# snc98_3x4_Switch-cherry_ml.net
KiCad netlist of a schematic drawn in EAGLE
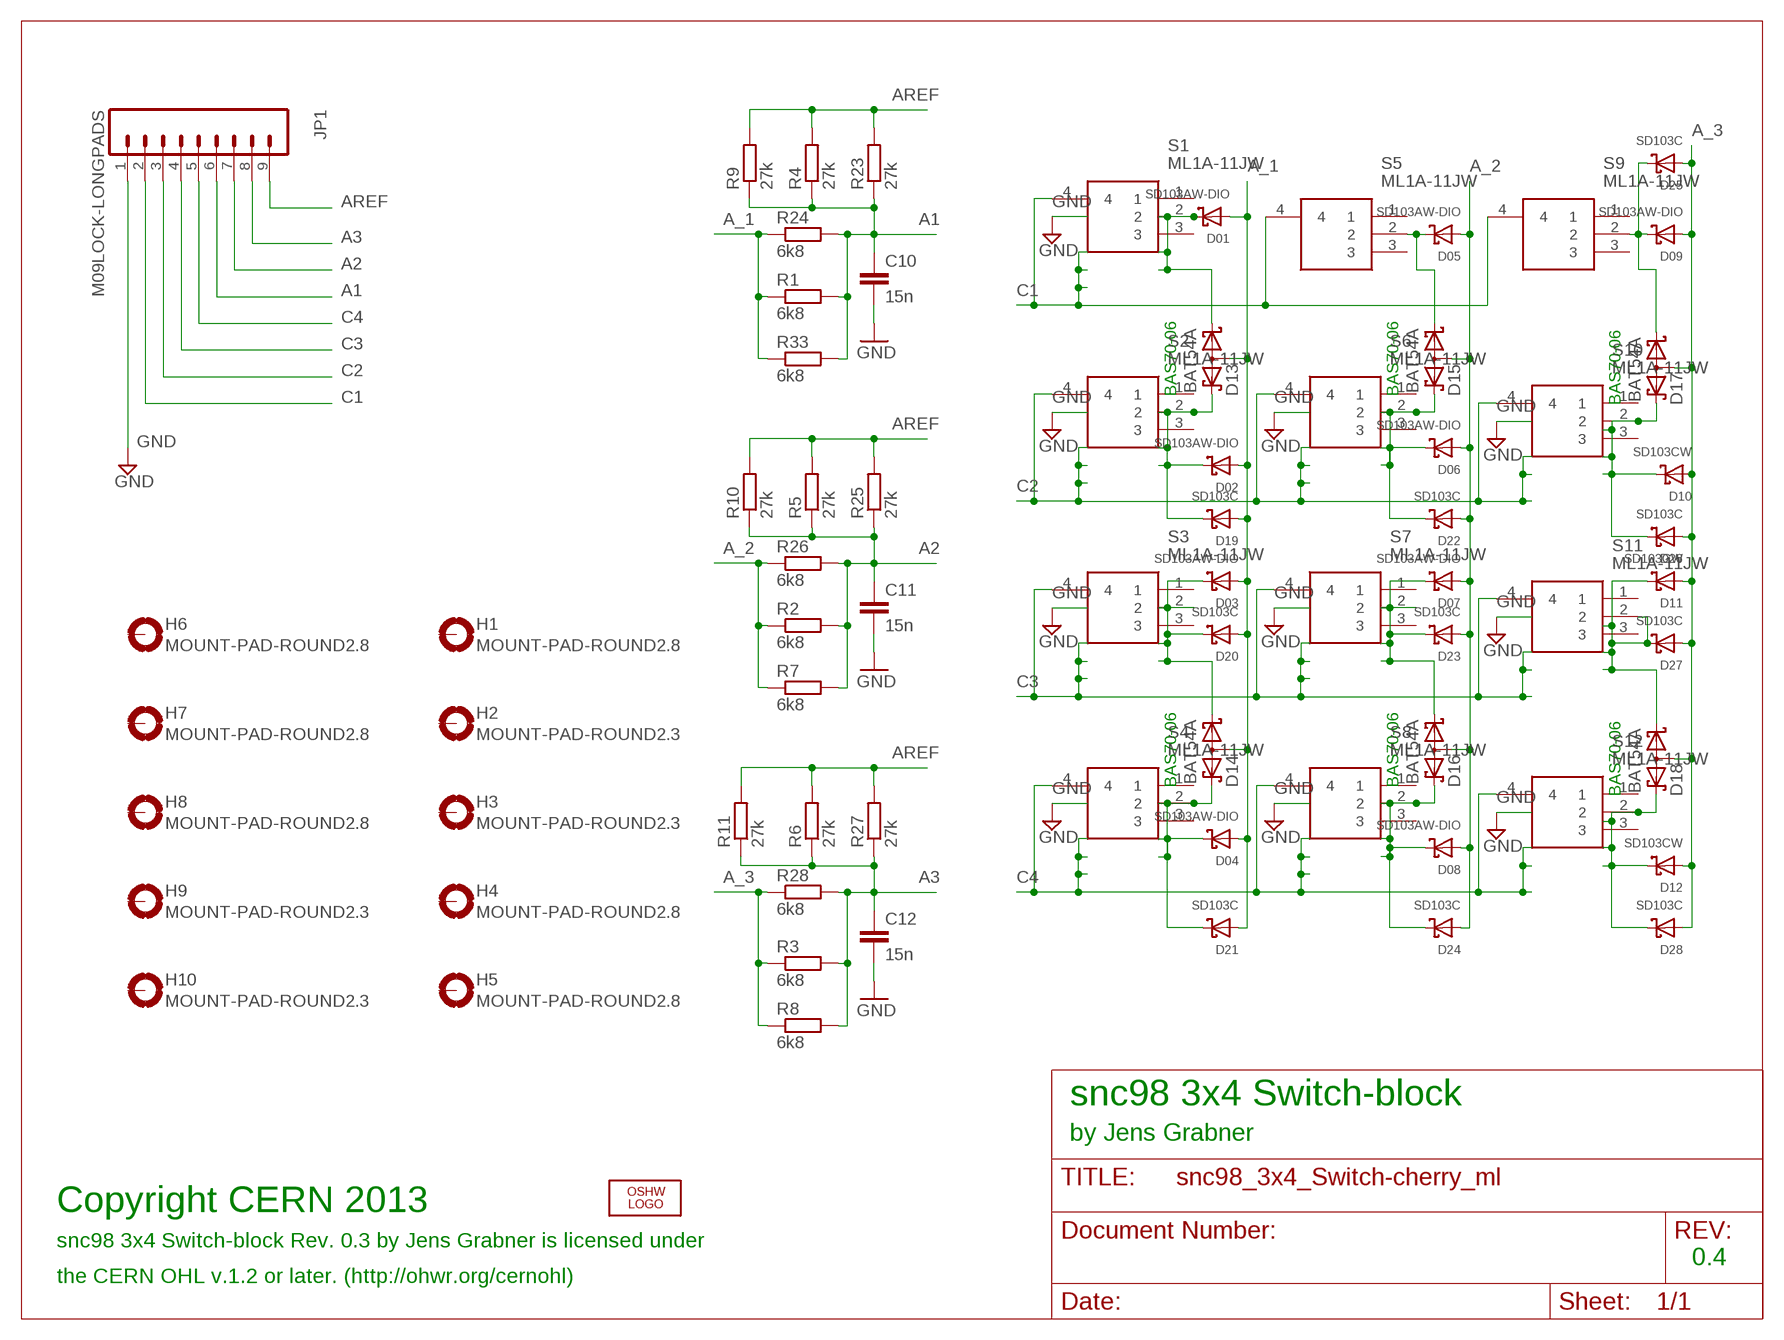
[diagram p0: schematic, sheet 1]

(export (version "E")
  (design (tool "Eeschema 10.0.6"))
  (components
    (comp (ref "C10")
      (value "15n")
      (footprint "eagle-import:C1206K")
      (libsource (lib "eagle-import") (part "C-EUC1206K"))
    )
    (comp (ref "C11")
      (value "15n")
      (footprint "eagle-import:C1206K")
      (libsource (lib "eagle-import") (part "C-EUC1206K"))
    )
    (comp (ref "C12")
      (value "15n")
      (footprint "eagle-import:C1206K")
      (libsource (lib "eagle-import") (part "C-EUC1206K"))
    )
    (comp (ref "D01")
      (value "SD103AW-DIO")
      (footprint "eagle-import:SOD-123F")
      (fields (field (name "MF") "MULTICOMP") (field (name "MPN") "SD103CW-7-F"))
      (libsource (lib "eagle-import") (part "DIODESOD-123F"))
    )
    (comp (ref "D02")
      (value "SD103AW-DIO")
      (footprint "eagle-import:SOD-123F")
      (fields (field (name "MF") "MULTICOMP") (field (name "MPN") "SD103CW-7-F"))
      (libsource (lib "eagle-import") (part "DIODESOD-123F"))
    )
    (comp (ref "D03")
      (value "SD103AW-DIO")
      (footprint "eagle-import:SOD-123F")
      (fields (field (name "MF") "MULTICOMP") (field (name "MPN") "SD103CW-7-F"))
      (libsource (lib "eagle-import") (part "DIODESOD-123F"))
    )
    (comp (ref "D04")
      (value "SD103AW-DIO")
      (footprint "eagle-import:SOD-123F")
      (fields (field (name "MF") "MULTICOMP") (field (name "MPN") "SD103CW-7-F"))
      (libsource (lib "eagle-import") (part "DIODESOD-123F"))
    )
    (comp (ref "D05")
      (value "SD103AW-DIO")
      (footprint "eagle-import:SOD-123F")
      (fields (field (name "MF") "MULTICOMP") (field (name "MPN") "SD103CW-7-F"))
      (libsource (lib "eagle-import") (part "DIODESOD-123F"))
    )
    (comp (ref "D06")
      (value "SD103AW-DIO")
      (footprint "eagle-import:SOD-123F")
      (fields (field (name "MF") "MULTICOMP") (field (name "MPN") "SD103CW-7-F"))
      (libsource (lib "eagle-import") (part "DIODESOD-123F"))
    )
    (comp (ref "D07")
      (value "SD103AW-DIO")
      (footprint "eagle-import:SOD-123F")
      (fields (field (name "MF") "MULTICOMP") (field (name "MPN") "SD103CW-7-F"))
      (libsource (lib "eagle-import") (part "DIODESOD-123F"))
    )
    (comp (ref "D08")
      (value "SD103AW-DIO")
      (footprint "eagle-import:SOD-123F")
      (fields (field (name "MF") "MULTICOMP") (field (name "MPN") "SD103CW-7-F"))
      (libsource (lib "eagle-import") (part "DIODESOD-123F"))
    )
    (comp (ref "D09")
      (value "SD103AW-DIO")
      (footprint "eagle-import:SOD-123F")
      (fields (field (name "MF") "MULTICOMP") (field (name "MPN") "SD103CW-7-F"))
      (libsource (lib "eagle-import") (part "DIODESOD-123F"))
    )
    (comp (ref "D10")
      (value "SD103CW")
      (footprint "eagle-import:SOD-123F")
      (fields (field (name "MF") "MULTICOMP") (field (name "MPN") "SD103CW-7-F"))
      (libsource (lib "eagle-import") (part "DIODESOD-123F"))
    )
    (comp (ref "D11")
      (value "SD103CW")
      (footprint "eagle-import:SOD-123F")
      (fields (field (name "MF") "MULTICOMP") (field (name "MPN") "SD103CW-7-F"))
      (libsource (lib "eagle-import") (part "DIODESOD-123F"))
    )
    (comp (ref "D12")
      (value "SD103CW")
      (footprint "eagle-import:SOD-123F")
      (fields (field (name "MF") "MULTICOMP") (field (name "MPN") "SD103CW-7-F"))
      (libsource (lib "eagle-import") (part "DIODESOD-123F"))
    )
    (comp (ref "D13")
      (value "BAT54A")
      (footprint "eagle-import:SOT23")
      (libsource (lib "eagle-import") (part "BAT54A"))
    )
    (comp (ref "D14")
      (value "BAT54A")
      (footprint "eagle-import:SOT23")
      (libsource (lib "eagle-import") (part "BAT54A"))
    )
    (comp (ref "D15")
      (value "BAT54A")
      (footprint "eagle-import:SOT23")
      (libsource (lib "eagle-import") (part "BAT54A"))
    )
    (comp (ref "D16")
      (value "BAT54A")
      (footprint "eagle-import:SOT23")
      (libsource (lib "eagle-import") (part "BAT54A"))
    )
    (comp (ref "D17")
      (value "BAT54A")
      (footprint "eagle-import:SOT23")
      (libsource (lib "eagle-import") (part "BAT54A"))
    )
    (comp (ref "D18")
      (value "BAT54A")
      (footprint "eagle-import:SOT23")
      (libsource (lib "eagle-import") (part "BAT54A"))
    )
    (comp (ref "D19")
      (value "SD103C")
      (footprint "eagle-import:280MIL-TH")
      (fields (field (name "MF") "MULTICOMP") (field (name "MPN") "SD103CW-7-F"))
      (libsource (lib "eagle-import") (part "DIODE280MIL-TH"))
    )
    (comp (ref "D20")
      (value "SD103C")
      (footprint "eagle-import:280MIL-TH")
      (fields (field (name "MF") "MULTICOMP") (field (name "MPN") "SD103CW-7-F"))
      (libsource (lib "eagle-import") (part "DIODE280MIL-TH"))
    )
    (comp (ref "D21")
      (value "SD103C")
      (footprint "eagle-import:280MIL-TH")
      (fields (field (name "MF") "MULTICOMP") (field (name "MPN") "SD103CW-7-F"))
      (libsource (lib "eagle-import") (part "DIODE280MIL-TH"))
    )
    (comp (ref "D22")
      (value "SD103C")
      (footprint "eagle-import:280MIL-TH")
      (fields (field (name "MF") "MULTICOMP") (field (name "MPN") "SD103CW-7-F"))
      (libsource (lib "eagle-import") (part "DIODE280MIL-TH"))
    )
    (comp (ref "D23")
      (value "SD103C")
      (footprint "eagle-import:280MIL-TH")
      (fields (field (name "MF") "MULTICOMP") (field (name "MPN") "SD103CW-7-F"))
      (libsource (lib "eagle-import") (part "DIODE280MIL-TH"))
    )
    (comp (ref "D24")
      (value "SD103C")
      (footprint "eagle-import:280MIL-TH")
      (fields (field (name "MF") "MULTICOMP") (field (name "MPN") "SD103CW-7-F"))
      (libsource (lib "eagle-import") (part "DIODE280MIL-TH"))
    )
    (comp (ref "D25")
      (value "SD103C")
      (footprint "eagle-import:280MIL-TH")
      (fields (field (name "MF") "MULTICOMP") (field (name "MPN") "SD103CW-7-F"))
      (libsource (lib "eagle-import") (part "DIODE280MIL-TH"))
    )
    (comp (ref "D26")
      (value "SD103C")
      (footprint "eagle-import:280MIL-TH")
      (fields (field (name "MF") "MULTICOMP") (field (name "MPN") "SD103CW-7-F"))
      (libsource (lib "eagle-import") (part "DIODE280MIL-TH"))
    )
    (comp (ref "D27")
      (value "SD103C")
      (footprint "eagle-import:280MIL-TH")
      (fields (field (name "MF") "MULTICOMP") (field (name "MPN") "SD103CW-7-F"))
      (libsource (lib "eagle-import") (part "DIODE280MIL-TH"))
    )
    (comp (ref "D28")
      (value "SD103C")
      (footprint "eagle-import:280MIL-TH")
      (fields (field (name "MF") "MULTICOMP") (field (name "MPN") "SD103CW-7-F"))
      (libsource (lib "eagle-import") (part "DIODE280MIL-TH"))
    )
    (comp (ref "H1")
      (value "MOUNT-PAD-ROUND2.8")
      (footprint "eagle-import:2,8-PAD")
      (libsource (lib "eagle-import") (part "MOUNT-PAD-ROUND2.8"))
    )
    (comp (ref "H2")
      (value "MOUNT-PAD-ROUND2.3")
      (footprint "eagle-import:2,3-PAD")
      (libsource (lib "eagle-import") (part "MOUNT-PAD-ROUND2.3"))
    )
    (comp (ref "H3")
      (value "MOUNT-PAD-ROUND2.3")
      (footprint "eagle-import:2,3-PAD")
      (libsource (lib "eagle-import") (part "MOUNT-PAD-ROUND2.3"))
    )
    (comp (ref "H4")
      (value "MOUNT-PAD-ROUND2.8")
      (footprint "eagle-import:2,8-PAD")
      (libsource (lib "eagle-import") (part "MOUNT-PAD-ROUND2.8"))
    )
    (comp (ref "H5")
      (value "MOUNT-PAD-ROUND2.8")
      (footprint "eagle-import:2,8-PAD")
      (libsource (lib "eagle-import") (part "MOUNT-PAD-ROUND2.8"))
    )
    (comp (ref "H6")
      (value "MOUNT-PAD-ROUND2.8")
      (footprint "eagle-import:2,8-PAD")
      (libsource (lib "eagle-import") (part "MOUNT-PAD-ROUND2.8"))
    )
    (comp (ref "H7")
      (value "MOUNT-PAD-ROUND2.8")
      (footprint "eagle-import:2,8-PAD")
      (libsource (lib "eagle-import") (part "MOUNT-PAD-ROUND2.8"))
    )
    (comp (ref "H8")
      (value "MOUNT-PAD-ROUND2.8")
      (footprint "eagle-import:2,8-PAD")
      (libsource (lib "eagle-import") (part "MOUNT-PAD-ROUND2.8"))
    )
    (comp (ref "H9")
      (value "MOUNT-PAD-ROUND2.3")
      (footprint "eagle-import:2,3-PAD")
      (libsource (lib "eagle-import") (part "MOUNT-PAD-ROUND2.3"))
    )
    (comp (ref "H10")
      (value "MOUNT-PAD-ROUND2.3")
      (footprint "eagle-import:2,3-PAD")
      (libsource (lib "eagle-import") (part "MOUNT-PAD-ROUND2.3"))
    )
    (comp (ref "JP1")
      (value "M09LOCK-LONGPADS")
      (footprint "eagle-import:1X09_LOCK_LONGPADS")
      (libsource (lib "eagle-import") (part "M09LOCK-LONGPADS"))
    )
    (comp (ref "LOGO1")
      (value "OSHW_LOGO_8MILX0150-NT")
      (footprint "eagle-import:OSHW_8X150_NOTEXT")
      (libsource (lib "eagle-import") (part "OSHW_LOGO_8MILX0150-NT"))
    )
    (comp (ref "R1")
      (value "6k8")
      (footprint "eagle-import:R1206")
      (libsource (lib "eagle-import") (part "R-EU_R1206"))
    )
    (comp (ref "R2")
      (value "6k8")
      (footprint "eagle-import:R1206")
      (libsource (lib "eagle-import") (part "R-EU_R1206"))
    )
    (comp (ref "R3")
      (value "6k8")
      (footprint "eagle-import:R1206")
      (libsource (lib "eagle-import") (part "R-EU_R1206"))
    )
    (comp (ref "R4")
      (value "27k")
      (footprint "eagle-import:R1206")
      (libsource (lib "eagle-import") (part "R-EU_R1206"))
    )
    (comp (ref "R5")
      (value "27k")
      (footprint "eagle-import:R1206")
      (libsource (lib "eagle-import") (part "R-EU_R1206"))
    )
    (comp (ref "R6")
      (value "27k")
      (footprint "eagle-import:R1206")
      (libsource (lib "eagle-import") (part "R-EU_R1206"))
    )
    (comp (ref "R7")
      (value "6k8")
      (footprint "eagle-import:M0805")
      (libsource (lib "eagle-import") (part "R-EU_M0805"))
    )
    (comp (ref "R8")
      (value "6k8")
      (footprint "eagle-import:M0805")
      (libsource (lib "eagle-import") (part "R-EU_M0805"))
    )
    (comp (ref "R9")
      (value "27k")
      (footprint "eagle-import:M0805")
      (libsource (lib "eagle-import") (part "R-EU_M0805"))
    )
    (comp (ref "R10")
      (value "27k")
      (footprint "eagle-import:M0805")
      (libsource (lib "eagle-import") (part "R-EU_M0805"))
    )
    (comp (ref "R11")
      (value "27k")
      (footprint "eagle-import:M0805")
      (libsource (lib "eagle-import") (part "R-EU_M0805"))
    )
    (comp (ref "R23")
      (value "27k")
      (footprint "eagle-import:0204_5")
      (libsource (lib "eagle-import") (part "R-EU_0204/5"))
    )
    (comp (ref "R24")
      (value "6k8")
      (footprint "eagle-import:0204_5")
      (libsource (lib "eagle-import") (part "R-EU_0204/5"))
    )
    (comp (ref "R25")
      (value "27k")
      (footprint "eagle-import:0204_5")
      (libsource (lib "eagle-import") (part "R-EU_0204/5"))
    )
    (comp (ref "R26")
      (value "6k8")
      (footprint "eagle-import:0204_5")
      (libsource (lib "eagle-import") (part "R-EU_0204/5"))
    )
    (comp (ref "R27")
      (value "27k")
      (footprint "eagle-import:0204_5")
      (libsource (lib "eagle-import") (part "R-EU_0204/5"))
    )
    (comp (ref "R28")
      (value "6k8")
      (footprint "eagle-import:0204_5")
      (libsource (lib "eagle-import") (part "R-EU_0204/5"))
    )
    (comp (ref "R33")
      (value "6k8")
      (footprint "eagle-import:M0805")
      (libsource (lib "eagle-import") (part "R-EU_M0805"))
    )
    (comp (ref "S1")
      (value "ML1A-11JW")
      (footprint "eagle-import:ML1A11JW")
      (fields (field (name "MOUSER_PART_NUMBER") "540-ML1A-11JW"))
      (libsource (lib "eagle-import") (part "ML1A-11JW"))
    )
    (comp (ref "S2")
      (value "ML1A-11JW")
      (footprint "eagle-import:ML1A11JW")
      (fields (field (name "MOUSER_PART_NUMBER") "540-ML1A-11JW"))
      (libsource (lib "eagle-import") (part "ML1A-11JW"))
    )
    (comp (ref "S3")
      (value "ML1A-11JW")
      (footprint "eagle-import:ML1A11JW")
      (fields (field (name "MOUSER_PART_NUMBER") "540-ML1A-11JW"))
      (libsource (lib "eagle-import") (part "ML1A-11JW"))
    )
    (comp (ref "S4")
      (value "ML1A-11JW")
      (footprint "eagle-import:ML1A11JW")
      (fields (field (name "MOUSER_PART_NUMBER") "540-ML1A-11JW"))
      (libsource (lib "eagle-import") (part "ML1A-11JW"))
    )
    (comp (ref "S5")
      (value "ML1A-11JW")
      (footprint "eagle-import:ML1A11JW")
      (fields (field (name "MOUSER_PART_NUMBER") "540-ML1A-11JW"))
      (libsource (lib "eagle-import") (part "ML1A-11JW"))
    )
    (comp (ref "S6")
      (value "ML1A-11JW")
      (footprint "eagle-import:ML1A11JW")
      (fields (field (name "MOUSER_PART_NUMBER") "540-ML1A-11JW"))
      (libsource (lib "eagle-import") (part "ML1A-11JW"))
    )
    (comp (ref "S7")
      (value "ML1A-11JW")
      (footprint "eagle-import:ML1A11JW")
      (fields (field (name "MOUSER_PART_NUMBER") "540-ML1A-11JW"))
      (libsource (lib "eagle-import") (part "ML1A-11JW"))
    )
    (comp (ref "S8")
      (value "ML1A-11JW")
      (footprint "eagle-import:ML1A11JW")
      (fields (field (name "MOUSER_PART_NUMBER") "540-ML1A-11JW"))
      (libsource (lib "eagle-import") (part "ML1A-11JW"))
    )
    (comp (ref "S9")
      (value "ML1A-11JW")
      (footprint "eagle-import:ML1A11JW")
      (fields (field (name "MOUSER_PART_NUMBER") "540-ML1A-11JW"))
      (libsource (lib "eagle-import") (part "ML1A-11JW"))
    )
    (comp (ref "S10")
      (value "ML1A-11JW")
      (footprint "eagle-import:ML1A11JW")
      (fields (field (name "MOUSER_PART_NUMBER") "540-ML1A-11JW"))
      (libsource (lib "eagle-import") (part "ML1A-11JW"))
    )
    (comp (ref "S11")
      (value "ML1A-11JW")
      (footprint "eagle-import:ML1A11JW")
      (fields (field (name "MOUSER_PART_NUMBER") "540-ML1A-11JW"))
      (libsource (lib "eagle-import") (part "ML1A-11JW"))
    )
    (comp (ref "S12")
      (value "ML1A-11JW")
      (footprint "eagle-import:ML1A11JW")
      (fields (field (name "MOUSER_PART_NUMBER") "540-ML1A-11JW"))
      (libsource (lib "eagle-import") (part "ML1A-11JW"))
    )
  )
  (nets
    (net (code "1") (name "/A1") (class "Default")
      (node (ref "C10") (pin "1") (pinfunction "1_1") (pintype "passive"))
      (node (ref "JP1") (pin "6") (pinfunction "6_6") (pintype "passive"))
      (node (ref "R1") (pin "2") (pinfunction "2_2") (pintype "passive"))
      (node (ref "R23") (pin "1") (pinfunction "1_1") (pintype "passive"))
      (node (ref "R24") (pin "2") (pinfunction "2_2") (pintype "passive"))
      (node (ref "R33") (pin "2") (pinfunction "2_2") (pintype "passive"))
      (node (ref "R4") (pin "1") (pinfunction "1_1") (pintype "passive"))
      (node (ref "R9") (pin "1") (pinfunction "1_1") (pintype "passive"))
    )
    (net (code "2") (name "/A2") (class "Default")
      (node (ref "C11") (pin "1") (pinfunction "1_1") (pintype "passive"))
      (node (ref "JP1") (pin "7") (pinfunction "7_7") (pintype "passive"))
      (node (ref "R10") (pin "1") (pinfunction "1_1") (pintype "passive"))
      (node (ref "R2") (pin "2") (pinfunction "2_2") (pintype "passive"))
      (node (ref "R25") (pin "1") (pinfunction "1_1") (pintype "passive"))
      (node (ref "R26") (pin "2") (pinfunction "2_2") (pintype "passive"))
      (node (ref "R5") (pin "1") (pinfunction "1_1") (pintype "passive"))
      (node (ref "R7") (pin "2") (pinfunction "2_2") (pintype "passive"))
    )
    (net (code "3") (name "/A3") (class "Default")
      (node (ref "C12") (pin "1") (pinfunction "1_1") (pintype "passive"))
      (node (ref "JP1") (pin "8") (pinfunction "8_8") (pintype "passive"))
      (node (ref "R11") (pin "1") (pinfunction "1_1") (pintype "passive"))
      (node (ref "R27") (pin "1") (pinfunction "1_1") (pintype "passive"))
      (node (ref "R28") (pin "2") (pinfunction "2_2") (pintype "passive"))
      (node (ref "R3") (pin "2") (pinfunction "2_2") (pintype "passive"))
      (node (ref "R6") (pin "1") (pinfunction "1_1") (pintype "passive"))
      (node (ref "R8") (pin "2") (pinfunction "2_2") (pintype "passive"))
    )
    (net (code "4") (name "/AREF") (class "Default")
      (node (ref "JP1") (pin "9") (pinfunction "9_9") (pintype "passive"))
      (node (ref "R10") (pin "2") (pinfunction "2_2") (pintype "passive"))
      (node (ref "R11") (pin "2") (pinfunction "2_2") (pintype "passive"))
      (node (ref "R23") (pin "2") (pinfunction "2_2") (pintype "passive"))
      (node (ref "R25") (pin "2") (pinfunction "2_2") (pintype "passive"))
      (node (ref "R27") (pin "2") (pinfunction "2_2") (pintype "passive"))
      (node (ref "R4") (pin "2") (pinfunction "2_2") (pintype "passive"))
      (node (ref "R5") (pin "2") (pinfunction "2_2") (pintype "passive"))
      (node (ref "R6") (pin "2") (pinfunction "2_2") (pintype "passive"))
      (node (ref "R9") (pin "2") (pinfunction "2_2") (pintype "passive"))
    )
    (net (code "5") (name "/A_1") (class "Default")
      (node (ref "D01") (pin "A") (pinfunction "A_A") (pintype "passive"))
      (node (ref "D02") (pin "A") (pinfunction "A_A") (pintype "passive"))
      (node (ref "D03") (pin "A") (pinfunction "A_A") (pintype "passive"))
      (node (ref "D04") (pin "A") (pinfunction "A_A") (pintype "passive"))
      (node (ref "D13") (pin "3") (pinfunction "AA_3") (pintype "passive"))
      (node (ref "D14") (pin "3") (pinfunction "AA_3") (pintype "passive"))
      (node (ref "D19") (pin "P$1") (pinfunction "A_P$1") (pintype "passive"))
      (node (ref "D20") (pin "P$1") (pinfunction "A_P$1") (pintype "passive"))
      (node (ref "D21") (pin "P$1") (pinfunction "A_P$1") (pintype "passive"))
      (node (ref "R1") (pin "1") (pinfunction "1_1") (pintype "passive"))
      (node (ref "R24") (pin "1") (pinfunction "1_1") (pintype "passive"))
      (node (ref "R33") (pin "1") (pinfunction "1_1") (pintype "passive"))
    )
    (net (code "6") (name "/A_2") (class "Default")
      (node (ref "D05") (pin "A") (pinfunction "A_A") (pintype "passive"))
      (node (ref "D06") (pin "A") (pinfunction "A_A") (pintype "passive"))
      (node (ref "D07") (pin "A") (pinfunction "A_A") (pintype "passive"))
      (node (ref "D08") (pin "A") (pinfunction "A_A") (pintype "passive"))
      (node (ref "D15") (pin "3") (pinfunction "AA_3") (pintype "passive"))
      (node (ref "D16") (pin "3") (pinfunction "AA_3") (pintype "passive"))
      (node (ref "D22") (pin "P$1") (pinfunction "A_P$1") (pintype "passive"))
      (node (ref "D23") (pin "P$1") (pinfunction "A_P$1") (pintype "passive"))
      (node (ref "D24") (pin "P$1") (pinfunction "A_P$1") (pintype "passive"))
      (node (ref "R2") (pin "1") (pinfunction "1_1") (pintype "passive"))
      (node (ref "R26") (pin "1") (pinfunction "1_1") (pintype "passive"))
      (node (ref "R7") (pin "1") (pinfunction "1_1") (pintype "passive"))
    )
    (net (code "7") (name "/A_3") (class "Default")
      (node (ref "D09") (pin "A") (pinfunction "A_A") (pintype "passive"))
      (node (ref "D10") (pin "A") (pinfunction "A_A") (pintype "passive"))
      (node (ref "D11") (pin "A") (pinfunction "A_A") (pintype "passive"))
      (node (ref "D12") (pin "A") (pinfunction "A_A") (pintype "passive"))
      (node (ref "D17") (pin "3") (pinfunction "AA_3") (pintype "passive"))
      (node (ref "D18") (pin "3") (pinfunction "AA_3") (pintype "passive"))
      (node (ref "D25") (pin "P$1") (pinfunction "A_P$1") (pintype "passive"))
      (node (ref "D26") (pin "P$1") (pinfunction "A_P$1") (pintype "passive"))
      (node (ref "D27") (pin "P$1") (pinfunction "A_P$1") (pintype "passive"))
      (node (ref "D28") (pin "P$1") (pinfunction "A_P$1") (pintype "passive"))
      (node (ref "R28") (pin "1") (pinfunction "1_1") (pintype "passive"))
      (node (ref "R3") (pin "1") (pinfunction "1_1") (pintype "passive"))
      (node (ref "R8") (pin "1") (pinfunction "1_1") (pintype "passive"))
    )
    (net (code "8") (name "/C1") (class "Default")
      (node (ref "JP1") (pin "2") (pinfunction "2_2") (pintype "passive"))
      (node (ref "S1") (pin "4") (pinfunction "4_4") (pintype "bidirectional"))
      (node (ref "S5") (pin "4") (pinfunction "4_4") (pintype "bidirectional"))
      (node (ref "S9") (pin "4") (pinfunction "4_4") (pintype "bidirectional"))
    )
    (net (code "9") (name "/C2") (class "Default")
      (node (ref "JP1") (pin "3") (pinfunction "3_3") (pintype "passive"))
      (node (ref "S10") (pin "4") (pinfunction "4_4") (pintype "bidirectional"))
      (node (ref "S2") (pin "4") (pinfunction "4_4") (pintype "bidirectional"))
      (node (ref "S6") (pin "4") (pinfunction "4_4") (pintype "bidirectional"))
    )
    (net (code "10") (name "/C3") (class "Default")
      (node (ref "JP1") (pin "4") (pinfunction "4_4") (pintype "passive"))
      (node (ref "S11") (pin "4") (pinfunction "4_4") (pintype "bidirectional"))
      (node (ref "S3") (pin "4") (pinfunction "4_4") (pintype "bidirectional"))
      (node (ref "S7") (pin "4") (pinfunction "4_4") (pintype "bidirectional"))
    )
    (net (code "11") (name "/C4") (class "Default")
      (node (ref "JP1") (pin "5") (pinfunction "5_5") (pintype "passive"))
      (node (ref "S12") (pin "4") (pinfunction "4_4") (pintype "bidirectional"))
      (node (ref "S4") (pin "4") (pinfunction "4_4") (pintype "bidirectional"))
      (node (ref "S8") (pin "4") (pinfunction "4_4") (pintype "bidirectional"))
    )
    (net (code "12") (name "GND") (class "Default")
      (node (ref "C10") (pin "2") (pinfunction "2_2") (pintype "passive"))
      (node (ref "C11") (pin "2") (pinfunction "2_2") (pintype "passive"))
      (node (ref "C12") (pin "2") (pinfunction "2_2") (pintype "passive"))
      (node (ref "JP1") (pin "1") (pinfunction "1_1") (pintype "passive"))
    )
    (net (code "13") (name "Net-(D13-K1)") (class "Default")
      (node (ref "D01") (pin "C") (pinfunction "C_C") (pintype "passive"))
      (node (ref "D13") (pin "1") (pinfunction "K1_1") (pintype "passive"))
      (node (ref "S1") (pin "2") (pinfunction "2_2") (pintype "bidirectional"))
    )
    (net (code "14") (name "Net-(D13-K2)") (class "Default")
      (node (ref "D02") (pin "C") (pinfunction "C_C") (pintype "passive"))
      (node (ref "D13") (pin "2") (pinfunction "K2_2") (pintype "passive"))
      (node (ref "D19") (pin "P$2") (pinfunction "C_P$2") (pintype "passive"))
      (node (ref "S2") (pin "2") (pinfunction "2_2") (pintype "bidirectional"))
    )
    (net (code "15") (name "Net-(D14-K1)") (class "Default")
      (node (ref "D03") (pin "C") (pinfunction "C_C") (pintype "passive"))
      (node (ref "D14") (pin "1") (pinfunction "K1_1") (pintype "passive"))
      (node (ref "D20") (pin "P$2") (pinfunction "C_P$2") (pintype "passive"))
      (node (ref "S3") (pin "2") (pinfunction "2_2") (pintype "bidirectional"))
    )
    (net (code "16") (name "Net-(D14-K2)") (class "Default")
      (node (ref "D04") (pin "C") (pinfunction "C_C") (pintype "passive"))
      (node (ref "D14") (pin "2") (pinfunction "K2_2") (pintype "passive"))
      (node (ref "D21") (pin "P$2") (pinfunction "C_P$2") (pintype "passive"))
      (node (ref "S4") (pin "2") (pinfunction "2_2") (pintype "bidirectional"))
    )
    (net (code "17") (name "Net-(D15-K1)") (class "Default")
      (node (ref "D05") (pin "C") (pinfunction "C_C") (pintype "passive"))
      (node (ref "D15") (pin "1") (pinfunction "K1_1") (pintype "passive"))
      (node (ref "S5") (pin "2") (pinfunction "2_2") (pintype "bidirectional"))
    )
    (net (code "18") (name "Net-(D15-K2)") (class "Default")
      (node (ref "D06") (pin "C") (pinfunction "C_C") (pintype "passive"))
      (node (ref "D15") (pin "2") (pinfunction "K2_2") (pintype "passive"))
      (node (ref "D22") (pin "P$2") (pinfunction "C_P$2") (pintype "passive"))
      (node (ref "S6") (pin "2") (pinfunction "2_2") (pintype "bidirectional"))
    )
    (net (code "19") (name "Net-(D16-K1)") (class "Default")
      (node (ref "D07") (pin "C") (pinfunction "C_C") (pintype "passive"))
      (node (ref "D16") (pin "1") (pinfunction "K1_1") (pintype "passive"))
      (node (ref "D23") (pin "P$2") (pinfunction "C_P$2") (pintype "passive"))
      (node (ref "S7") (pin "2") (pinfunction "2_2") (pintype "bidirectional"))
    )
    (net (code "20") (name "Net-(D16-K2)") (class "Default")
      (node (ref "D08") (pin "C") (pinfunction "C_C") (pintype "passive"))
      (node (ref "D16") (pin "2") (pinfunction "K2_2") (pintype "passive"))
      (node (ref "D24") (pin "P$2") (pinfunction "C_P$2") (pintype "passive"))
      (node (ref "S8") (pin "2") (pinfunction "2_2") (pintype "bidirectional"))
    )
    (net (code "21") (name "Net-(D17-K1)") (class "Default")
      (node (ref "D09") (pin "C") (pinfunction "C_C") (pintype "passive"))
      (node (ref "D17") (pin "1") (pinfunction "K1_1") (pintype "passive"))
      (node (ref "D25") (pin "P$2") (pinfunction "C_P$2") (pintype "passive"))
      (node (ref "S9") (pin "2") (pinfunction "2_2") (pintype "bidirectional"))
    )
    (net (code "22") (name "Net-(D17-K2)") (class "Default")
      (node (ref "D10") (pin "C") (pinfunction "C_C") (pintype "passive"))
      (node (ref "D17") (pin "2") (pinfunction "K2_2") (pintype "passive"))
      (node (ref "D26") (pin "P$2") (pinfunction "C_P$2") (pintype "passive"))
      (node (ref "S10") (pin "2") (pinfunction "2_2") (pintype "bidirectional"))
    )
    (net (code "23") (name "Net-(D18-K1)") (class "Default")
      (node (ref "D11") (pin "C") (pinfunction "C_C") (pintype "passive"))
      (node (ref "D18") (pin "1") (pinfunction "K1_1") (pintype "passive"))
      (node (ref "D27") (pin "P$2") (pinfunction "C_P$2") (pintype "passive"))
      (node (ref "S11") (pin "2") (pinfunction "2_2") (pintype "bidirectional"))
    )
    (net (code "24") (name "Net-(D18-K2)") (class "Default")
      (node (ref "D12") (pin "C") (pinfunction "C_C") (pintype "passive"))
      (node (ref "D18") (pin "2") (pinfunction "K2_2") (pintype "passive"))
      (node (ref "D28") (pin "P$2") (pinfunction "C_P$2") (pintype "passive"))
      (node (ref "S12") (pin "2") (pinfunction "2_2") (pintype "bidirectional"))
    )
    (net (code "25") (name "unconnected-(H1-MOUNT-PadB2,8)") (class "Default")
      (node (ref "H1") (pin "B2,8") (pinfunction "MOUNT_B2,8") (pintype "passive"))
    )
    (net (code "26") (name "unconnected-(H2-MOUNT-PadB2,8)") (class "Default")
      (node (ref "H2") (pin "B2,8") (pinfunction "MOUNT_B2,8") (pintype "passive"))
    )
    (net (code "27") (name "unconnected-(H3-MOUNT-PadB2,8)") (class "Default")
      (node (ref "H3") (pin "B2,8") (pinfunction "MOUNT_B2,8") (pintype "passive"))
    )
    (net (code "28") (name "unconnected-(H4-MOUNT-PadB2,8)") (class "Default")
      (node (ref "H4") (pin "B2,8") (pinfunction "MOUNT_B2,8") (pintype "passive"))
    )
    (net (code "29") (name "unconnected-(H5-MOUNT-PadB2,8)") (class "Default")
      (node (ref "H5") (pin "B2,8") (pinfunction "MOUNT_B2,8") (pintype "passive"))
    )
    (net (code "30") (name "unconnected-(H6-MOUNT-PadB2,8)") (class "Default")
      (node (ref "H6") (pin "B2,8") (pinfunction "MOUNT_B2,8") (pintype "passive"))
    )
    (net (code "31") (name "unconnected-(H7-MOUNT-PadB2,8)") (class "Default")
      (node (ref "H7") (pin "B2,8") (pinfunction "MOUNT_B2,8") (pintype "passive"))
    )
    (net (code "32") (name "unconnected-(H8-MOUNT-PadB2,8)") (class "Default")
      (node (ref "H8") (pin "B2,8") (pinfunction "MOUNT_B2,8") (pintype "passive"))
    )
    (net (code "33") (name "unconnected-(H9-MOUNT-PadB2,8)") (class "Default")
      (node (ref "H9") (pin "B2,8") (pinfunction "MOUNT_B2,8") (pintype "passive"))
    )
    (net (code "34") (name "unconnected-(H10-MOUNT-PadB2,8)") (class "Default")
      (node (ref "H10") (pin "B2,8") (pinfunction "MOUNT_B2,8") (pintype "passive"))
    )
    (net (code "35") (name "unconnected-(S1-Pad1)") (class "Default")
      (node (ref "S1") (pin "1") (pinfunction "1_1") (pintype "bidirectional"))
    )
    (net (code "36") (name "unconnected-(S1-Pad3)") (class "Default")
      (node (ref "S1") (pin "3") (pinfunction "3_3") (pintype "bidirectional"))
    )
    (net (code "37") (name "unconnected-(S2-Pad1)") (class "Default")
      (node (ref "S2") (pin "1") (pinfunction "1_1") (pintype "bidirectional"))
    )
    (net (code "38") (name "unconnected-(S2-Pad3)") (class "Default")
      (node (ref "S2") (pin "3") (pinfunction "3_3") (pintype "bidirectional"))
    )
    (net (code "39") (name "unconnected-(S3-Pad1)") (class "Default")
      (node (ref "S3") (pin "1") (pinfunction "1_1") (pintype "bidirectional"))
    )
    (net (code "40") (name "unconnected-(S3-Pad3)") (class "Default")
      (node (ref "S3") (pin "3") (pinfunction "3_3") (pintype "bidirectional"))
    )
    (net (code "41") (name "unconnected-(S4-Pad1)") (class "Default")
      (node (ref "S4") (pin "1") (pinfunction "1_1") (pintype "bidirectional"))
    )
    (net (code "42") (name "unconnected-(S4-Pad3)") (class "Default")
      (node (ref "S4") (pin "3") (pinfunction "3_3") (pintype "bidirectional"))
    )
    (net (code "43") (name "unconnected-(S5-Pad1)") (class "Default")
      (node (ref "S5") (pin "1") (pinfunction "1_1") (pintype "bidirectional"))
    )
    (net (code "44") (name "unconnected-(S5-Pad3)") (class "Default")
      (node (ref "S5") (pin "3") (pinfunction "3_3") (pintype "bidirectional"))
    )
    (net (code "45") (name "unconnected-(S6-Pad1)") (class "Default")
      (node (ref "S6") (pin "1") (pinfunction "1_1") (pintype "bidirectional"))
    )
    (net (code "46") (name "unconnected-(S6-Pad3)") (class "Default")
      (node (ref "S6") (pin "3") (pinfunction "3_3") (pintype "bidirectional"))
    )
    (net (code "47") (name "unconnected-(S7-Pad1)") (class "Default")
      (node (ref "S7") (pin "1") (pinfunction "1_1") (pintype "bidirectional"))
    )
    (net (code "48") (name "unconnected-(S7-Pad3)") (class "Default")
      (node (ref "S7") (pin "3") (pinfunction "3_3") (pintype "bidirectional"))
    )
    (net (code "49") (name "unconnected-(S8-Pad1)") (class "Default")
      (node (ref "S8") (pin "1") (pinfunction "1_1") (pintype "bidirectional"))
    )
    (net (code "50") (name "unconnected-(S8-Pad3)") (class "Default")
      (node (ref "S8") (pin "3") (pinfunction "3_3") (pintype "bidirectional"))
    )
    (net (code "51") (name "unconnected-(S9-Pad1)") (class "Default")
      (node (ref "S9") (pin "1") (pinfunction "1_1") (pintype "bidirectional"))
    )
    (net (code "52") (name "unconnected-(S9-Pad3)") (class "Default")
      (node (ref "S9") (pin "3") (pinfunction "3_3") (pintype "bidirectional"))
    )
    (net (code "53") (name "unconnected-(S10-Pad1)") (class "Default")
      (node (ref "S10") (pin "1") (pinfunction "1_1") (pintype "bidirectional"))
    )
    (net (code "54") (name "unconnected-(S10-Pad3)") (class "Default")
      (node (ref "S10") (pin "3") (pinfunction "3_3") (pintype "bidirectional"))
    )
    (net (code "55") (name "unconnected-(S11-Pad1)") (class "Default")
      (node (ref "S11") (pin "1") (pinfunction "1_1") (pintype "bidirectional"))
    )
    (net (code "56") (name "unconnected-(S11-Pad3)") (class "Default")
      (node (ref "S11") (pin "3") (pinfunction "3_3") (pintype "bidirectional"))
    )
    (net (code "57") (name "unconnected-(S12-Pad1)") (class "Default")
      (node (ref "S12") (pin "1") (pinfunction "1_1") (pintype "bidirectional"))
    )
    (net (code "58") (name "unconnected-(S12-Pad3)") (class "Default")
      (node (ref "S12") (pin "3") (pinfunction "3_3") (pintype "bidirectional"))
    )
  )
)
